# Sturing_Temperatuur_Bout.net
KiCad netlist of a schematic drawn in Altium Designer
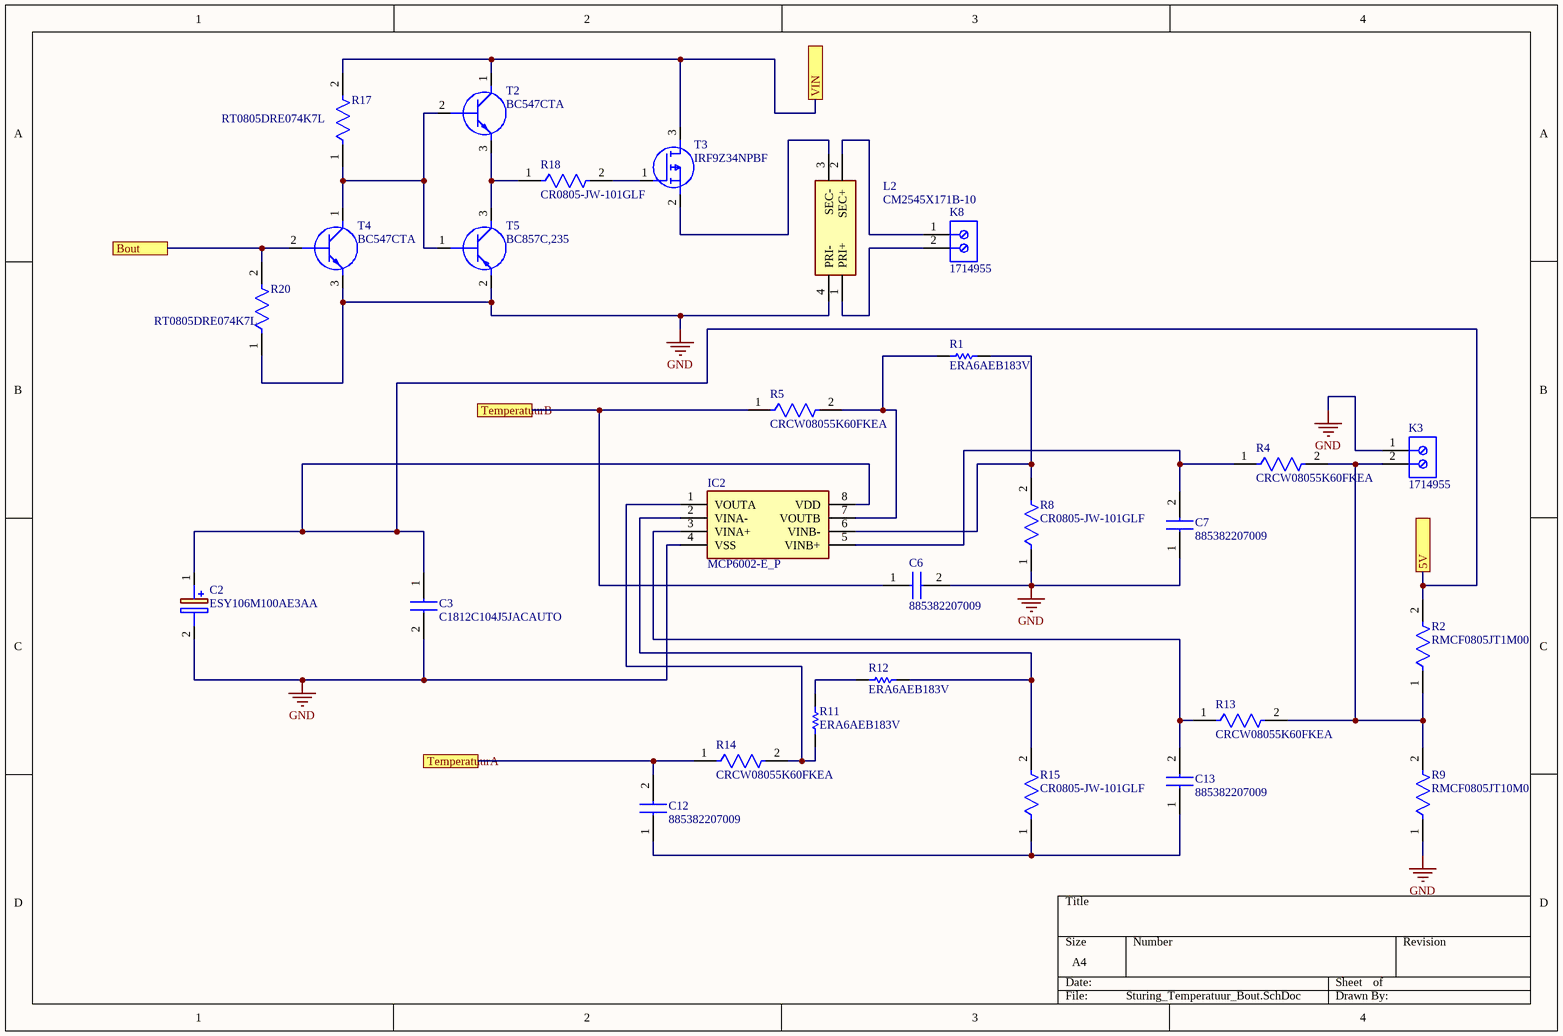
[diagram p0: Sturing_Temperatuur_Bout.SchDoc]

(export (version "E")
  (design (tool "Eeschema 10.0.6"))
  (components
    (comp (ref "C2")
      (value "ESY106M100AE3AA")
      (footprint "SamacSys:CAPPRD250W50D630H1250")
      (description "Capacitor Polarised")
      (libsource (lib "*") (part "ESY106M100AE3AA"))
    )
    (comp (ref "C3")
      (value "C1812C104J5JACAUTO")
      (footprint "SamacSys:CAPC4532X110N")
      (description "Capacitor")
      (libsource (lib "*") (part "C1812C104J5JACAUTO"))
    )
    (comp (ref "C6")
      (value "885382207009")
      (footprint "SamacSys:CAPC2012X135N")
      (description "Capacitor")
      (libsource (lib "*") (part "885382207009"))
    )
    (comp (ref "C7")
      (value "885382207009")
      (footprint "SamacSys:CAPC2012X135N")
      (description "Capacitor")
      (libsource (lib "*") (part "885382207009"))
    )
    (comp (ref "C12")
      (value "885382207009")
      (footprint "SamacSys:CAPC2012X135N")
      (description "Capacitor")
      (libsource (lib "*") (part "885382207009"))
    )
    (comp (ref "C13")
      (value "885382207009")
      (footprint "SamacSys:CAPC2012X135N")
      (description "Capacitor")
      (libsource (lib "*") (part "885382207009"))
    )
    (comp (ref "IC2")
      (value "MCP6002-E_P")
      (footprint "SamacSys:DIP781W56P254L950H533Q8N")
      (description "Integrated Circuit")
      (fields
        (field (name "MOUSER2 PART NUMBER") "579-MCP6002-E/P")
        (field (name "MANUFACTURER_PART_NUMBER") "MCP6002-E/P")
      )
      (libsource (lib "*") (part "MCP6002-E_P"))
    )
    (comp (ref "K3")
      (value "1714955")
      (footprint "PHOE-1714955_V")
      (description "PC Terminal Block, Pitch 6.35 mm, 1 x 2 Position, Height 21.5 mm, Tail Lenght 5.1 mm, RoHS, Bulk")
      (fields (field (name "MANUFACTURER") "Phoenix Contact"))
      (libsource (lib "Altium Content Vault") (part "CN-1P-F-TB2"))
    )
    (comp (ref "K8")
      (value "1714955")
      (footprint "PHOE-1714955_V")
      (description "PC Terminal Block, Pitch 6.35 mm, 1 x 2 Position, Height 21.5 mm, Tail Lenght 5.1 mm, RoHS, Bulk")
      (fields (field (name "MANUFACTURER") "Phoenix Contact"))
      (libsource (lib "Altium Content Vault") (part "CN-1P-F-TB2"))
    )
    (comp (ref "L2")
      (value "CM2545X171B-10")
      (footprint "SamacSys:CM2545X171B10")
      (description "Transformer")
      (libsource (lib "*") (part "CM2545X171B-10"))
    )
    (comp (ref "R1")
      (value "ERA6AEB183V")
      (footprint "RESC2013X60X40LL20T25")
      (fields (field (name "MANUFACTURER") "Panasonic"))
      (libsource (lib "Altium Content Vault") (part "RES"))
    )
    (comp (ref "R2")
      (value "RMCF0805JT1M00")
      (footprint "FP-RMCF0805-IPC_C")
      (description "1MΩ ±5% 0.125W 0805 Thick Film Chip Resistor AEC-Q200 compliant")
      (fields (field (name "TOLERANCE") "5%"))
      (libsource (lib "Altium Content Vault") (part "1029c3af85768c4190bb7ad29bc67b5"))
    )
    (comp (ref "R4")
      (value "CRCW08055K60FKEA")
      (footprint "FP-CRCW0805-e3-IPC_A")
      (description "RES Thick Film, 5.6kΩ, 1%, 0.125W, 100ppm/°C, 0805")
      (fields (field (name "TOLERANCE") "1%"))
      (libsource (lib "Altium Content Vault") (part "1029c3af85768c4190bb7ad29bc67b5"))
    )
    (comp (ref "R5")
      (value "CRCW08055K60FKEA")
      (footprint "FP-CRCW0805-e3-IPC_A")
      (description "RES Thick Film, 5.6kΩ, 1%, 0.125W, 100ppm/°C, 0805")
      (fields (field (name "TOLERANCE") "1%"))
      (libsource (lib "Altium Content Vault") (part "1029c3af85768c4190bb7ad29bc67b5"))
    )
    (comp (ref "R8")
      (value "CR0805-JW-101GLF")
      (footprint "FP-CR0805-IPC_A")
      (description "Thick Film Chip Resistors 0805 100Ω 0.125W 5% 200ppm/°C")
      (fields (field (name "TOLERANCE") "5%"))
      (libsource (lib "Altium Content Vault") (part "1029c3af85768c4190bb7ad29bc67b5"))
    )
    (comp (ref "R9")
      (value "RMCF0805JT10M0")
      (footprint "FP-RMCF0805-IPC_A")
      (description "10MΩ ±5% 0.125W 0805 Thick Film Chip Resistor AEC-Q200 compliant")
      (fields (field (name "TOLERANCE") "5%"))
      (libsource (lib "Altium Content Vault") (part "1029c3af85768c4190bb7ad29bc67b5"))
    )
    (comp (ref "R11")
      (value "ERA6AEB183V")
      (footprint "RESC2013X60X40LL20T25")
      (fields (field (name "MANUFACTURER") "Panasonic"))
      (libsource (lib "Altium Content Vault") (part "RES"))
    )
    (comp (ref "R12")
      (value "ERA6AEB183V")
      (footprint "RESC2013X60X40LL20T25")
      (fields (field (name "MANUFACTURER") "Panasonic"))
      (libsource (lib "Altium Content Vault") (part "RES"))
    )
    (comp (ref "R13")
      (value "CRCW08055K60FKEA")
      (footprint "FP-CRCW0805-e3-IPC_A")
      (description "RES Thick Film, 5.6kΩ, 1%, 0.125W, 100ppm/°C, 0805")
      (fields (field (name "TOLERANCE") "1%"))
      (libsource (lib "Altium Content Vault") (part "1029c3af85768c4190bb7ad29bc67b5"))
    )
    (comp (ref "R14")
      (value "CRCW08055K60FKEA")
      (footprint "FP-CRCW0805-e3-IPC_A")
      (description "RES Thick Film, 5.6kΩ, 1%, 0.125W, 100ppm/°C, 0805")
      (fields (field (name "TOLERANCE") "1%"))
      (libsource (lib "Altium Content Vault") (part "1029c3af85768c4190bb7ad29bc67b5"))
    )
    (comp (ref "R15")
      (value "CR0805-JW-101GLF")
      (footprint "FP-CR0805-IPC_A")
      (description "Thick Film Chip Resistors 0805 100Ω 0.125W 5% 200ppm/°C")
      (fields (field (name "TOLERANCE") "5%"))
      (libsource (lib "Altium Content Vault") (part "1029c3af85768c4190bb7ad29bc67b5"))
    )
    (comp (ref "R17")
      (value "RT0805DRE074K7L")
      (footprint "FP-RT0805-MFG")
      (description "RES SMD 4.7K OHM 0.5% 1/8W 0805")
      (fields
        (field (name "OCTOPART") "https://octopart.com/rt0805dre074k7l-yageo-1242027")
        (field (name "TOLERANCE") "0.01")
      )
      (libsource (lib "Altium Content Vault") (part "1029c3af85768c4190bb7ad29bc67b5"))
    )
    (comp (ref "R18")
      (value "CR0805-JW-101GLF")
      (footprint "FP-CR0805-IPC_A")
      (description "Thick Film Chip Resistors 0805 100Ω 0.125W 5% 200ppm/°C")
      (fields (field (name "TOLERANCE") "5%"))
      (libsource (lib "Altium Content Vault") (part "1029c3af85768c4190bb7ad29bc67b5"))
    )
    (comp (ref "R20")
      (value "RT0805DRE074K7L")
      (footprint "FP-RT0805-MFG")
      (description "RES SMD 4.7K OHM 0.5% 1/8W 0805")
      (fields
        (field (name "OCTOPART") "https://octopart.com/rt0805dre074k7l-yageo-1242027")
        (field (name "TOLERANCE") "0.01")
      )
      (libsource (lib "Altium Content Vault") (part "1029c3af85768c4190bb7ad29bc67b5"))
    )
    (comp (ref "T2")
      (value "BC547CTA")
      (footprint "SamacSys:MC79L15ACPG")
      (description "Transistor BJT NPN")
      (libsource (lib "*") (part "BC547CTA"))
    )
    (comp (ref "T3")
      (value "IRF9Z34NPBF")
      (footprint "SamacSys:TO254P469X1042X1967-3P")
      (description "MOSFET (P-Channel)")
      (fields (field (name "MOUSER2 PART NUMBER") "942-IRF9Z34NPBF"))
      (libsource (lib "*") (part "IRF9Z34NPBF"))
    )
    (comp (ref "T4")
      (value "BC547CTA")
      (footprint "SamacSys:MC79L15ACPG")
      (description "Transistor BJT NPN")
      (libsource (lib "*") (part "BC547CTA"))
    )
    (comp (ref "T5")
      (value "BC857C,235")
      (footprint "SamacSys:SOT95P230X110-3N")
      (description "Transistor BJT PNP")
      (fields (field (name "MOUSER2 PART NUMBER") "771-BC857C235"))
      (libsource (lib "*") (part "BC857C,235"))
    )
  )
  (nets
    (net (code "1") (name "/5V") (class "Default")
      (node (ref "C2") (pin "1") (pinfunction "+_1") (pintype "passive"))
      (node (ref "C3") (pin "1") (pinfunction "1_1") (pintype "passive"))
      (node (ref "IC2") (pin "8") (pinfunction "VDD_8") (pintype "passive"))
      (node (ref "R2") (pin "2") (pinfunction "2_2") (pintype "passive"))
    )
    (net (code "2") (name "/Bout") (class "Default")
      (node (ref "R20") (pin "2") (pinfunction "2_2") (pintype "passive"))
      (node (ref "T4") (pin "2") (pinfunction "B_2") (pintype "passive"))
    )
    (net (code "3") (name "/TemperatuurA") (class "Default")
      (node (ref "C12") (pin "2") (pinfunction "2_2") (pintype "passive"))
      (node (ref "R14") (pin "1") (pinfunction "1_1") (pintype "passive"))
    )
    (net (code "4") (name "/TemperatuurB") (class "Default")
      (node (ref "C6") (pin "1") (pinfunction "1_1") (pintype "passive"))
      (node (ref "R5") (pin "1") (pinfunction "1_1") (pintype "passive"))
    )
    (net (code "5") (name "/VIN") (class "Default")
      (node (ref "R17") (pin "2") (pinfunction "2_2") (pintype "passive"))
      (node (ref "T2") (pin "1") (pinfunction "C_1") (pintype "passive"))
      (node (ref "T3") (pin "3") (pinfunction "D_3") (pintype "passive"))
    )
    (net (code "6") (name "GND") (class "Default")
      (node (ref "C2") (pin "2") (pinfunction "-_2") (pintype "passive"))
      (node (ref "C3") (pin "2") (pinfunction "2_2") (pintype "passive"))
      (node (ref "C6") (pin "2") (pinfunction "2_2") (pintype "passive"))
      (node (ref "C7") (pin "1") (pinfunction "1_1") (pintype "passive"))
      (node (ref "IC2") (pin "4") (pinfunction "VSS_4") (pintype "passive"))
      (node (ref "K3") (pin "1") (pinfunction "1_1") (pintype "passive"))
      (node (ref "L2") (pin "4") (pinfunction "PRI-_4") (pintype "passive"))
      (node (ref "R20") (pin "1") (pinfunction "1_1") (pintype "passive"))
      (node (ref "R8") (pin "1") (pinfunction "1_1") (pintype "passive"))
      (node (ref "R9") (pin "1") (pinfunction "1_1") (pintype "passive"))
      (node (ref "T4") (pin "3") (pinfunction "E_3") (pintype "passive"))
      (node (ref "T5") (pin "2") (pinfunction "E_2") (pintype "passive"))
    )
    (net (code "7") (name "Net-(C12-Pad1)") (class "Default")
      (node (ref "C12") (pin "1") (pinfunction "1_1") (pintype "passive"))
      (node (ref "C13") (pin "1") (pinfunction "1_1") (pintype "passive"))
      (node (ref "R15") (pin "1") (pinfunction "1_1") (pintype "passive"))
    )
    (net (code "8") (name "Net-(IC2-VINA+)") (class "Default")
      (node (ref "C13") (pin "2") (pinfunction "2_2") (pintype "passive"))
      (node (ref "IC2") (pin "3") (pinfunction "VINA+_3") (pintype "passive"))
      (node (ref "R13") (pin "1") (pinfunction "1_1") (pintype "passive"))
    )
    (net (code "9") (name "Net-(IC2-VINA-)") (class "Default")
      (node (ref "IC2") (pin "2") (pinfunction "VINA-_2") (pintype "passive"))
      (node (ref "R12") (pin "2") (pinfunction "2_2") (pintype "passive"))
      (node (ref "R15") (pin "2") (pinfunction "2_2") (pintype "passive"))
    )
    (net (code "10") (name "Net-(IC2-VINB+)") (class "Default")
      (node (ref "C7") (pin "2") (pinfunction "2_2") (pintype "passive"))
      (node (ref "IC2") (pin "5") (pinfunction "VINB+_5") (pintype "passive"))
      (node (ref "R4") (pin "1") (pinfunction "1_1") (pintype "passive"))
    )
    (net (code "11") (name "Net-(IC2-VINB-)") (class "Default")
      (node (ref "IC2") (pin "6") (pinfunction "VINB-_6") (pintype "passive"))
      (node (ref "R1") (pin "2") (pinfunction "2_2") (pintype "passive"))
      (node (ref "R8") (pin "2") (pinfunction "2_2") (pintype "passive"))
    )
    (net (code "12") (name "Net-(IC2-VOUTA)") (class "Default")
      (node (ref "IC2") (pin "1") (pinfunction "VOUTA_1") (pintype "passive"))
      (node (ref "R11") (pin "1") (pinfunction "1_1") (pintype "passive"))
      (node (ref "R14") (pin "2") (pinfunction "2_2") (pintype "passive"))
    )
    (net (code "13") (name "Net-(IC2-VOUTB)") (class "Default")
      (node (ref "IC2") (pin "7") (pinfunction "VOUTB_7") (pintype "passive"))
      (node (ref "R1") (pin "1") (pinfunction "1_1") (pintype "passive"))
      (node (ref "R5") (pin "2") (pinfunction "2_2") (pintype "passive"))
    )
    (net (code "14") (name "Net-(K3-Pad2)") (class "Default")
      (node (ref "K3") (pin "2") (pinfunction "2_2") (pintype "passive"))
      (node (ref "R13") (pin "2") (pinfunction "2_2") (pintype "passive"))
      (node (ref "R2") (pin "1") (pinfunction "1_1") (pintype "passive"))
      (node (ref "R4") (pin "2") (pinfunction "2_2") (pintype "passive"))
      (node (ref "R9") (pin "2") (pinfunction "2_2") (pintype "passive"))
    )
    (net (code "15") (name "Net-(L2-PRI+)") (class "Default")
      (node (ref "K8") (pin "2") (pinfunction "2_2") (pintype "passive"))
      (node (ref "L2") (pin "1") (pinfunction "PRI+_1") (pintype "passive"))
    )
    (net (code "16") (name "Net-(L2-SEC+)") (class "Default")
      (node (ref "K8") (pin "1") (pinfunction "1_1") (pintype "passive"))
      (node (ref "L2") (pin "2") (pinfunction "SEC+_2") (pintype "passive"))
    )
    (net (code "17") (name "Net-(L2-SEC-)") (class "Default")
      (node (ref "L2") (pin "3") (pinfunction "SEC-_3") (pintype "passive"))
      (node (ref "T3") (pin "2") (pinfunction "S_2") (pintype "passive"))
    )
    (net (code "18") (name "Net-(R11-Pad2)") (class "Default")
      (node (ref "R11") (pin "2") (pinfunction "2_2") (pintype "passive"))
      (node (ref "R12") (pin "1") (pinfunction "1_1") (pintype "passive"))
    )
    (net (code "19") (name "Net-(T2-B)") (class "Default")
      (node (ref "R17") (pin "1") (pinfunction "1_1") (pintype "passive"))
      (node (ref "T2") (pin "2") (pinfunction "B_2") (pintype "passive"))
      (node (ref "T4") (pin "1") (pinfunction "C_1") (pintype "passive"))
      (node (ref "T5") (pin "1") (pinfunction "B_1") (pintype "passive"))
    )
    (net (code "20") (name "Net-(T2-E)") (class "Default")
      (node (ref "R18") (pin "1") (pinfunction "1_1") (pintype "passive"))
      (node (ref "T2") (pin "3") (pinfunction "E_3") (pintype "passive"))
      (node (ref "T5") (pin "3") (pinfunction "C_3") (pintype "passive"))
    )
    (net (code "21") (name "Net-(T3-G)") (class "Default")
      (node (ref "R18") (pin "2") (pinfunction "2_2") (pintype "passive"))
      (node (ref "T3") (pin "1") (pinfunction "G_1") (pintype "passive"))
    )
  )
)
